# multi_sense32.net
KiCad netlist of a schematic drawn in EAGLE
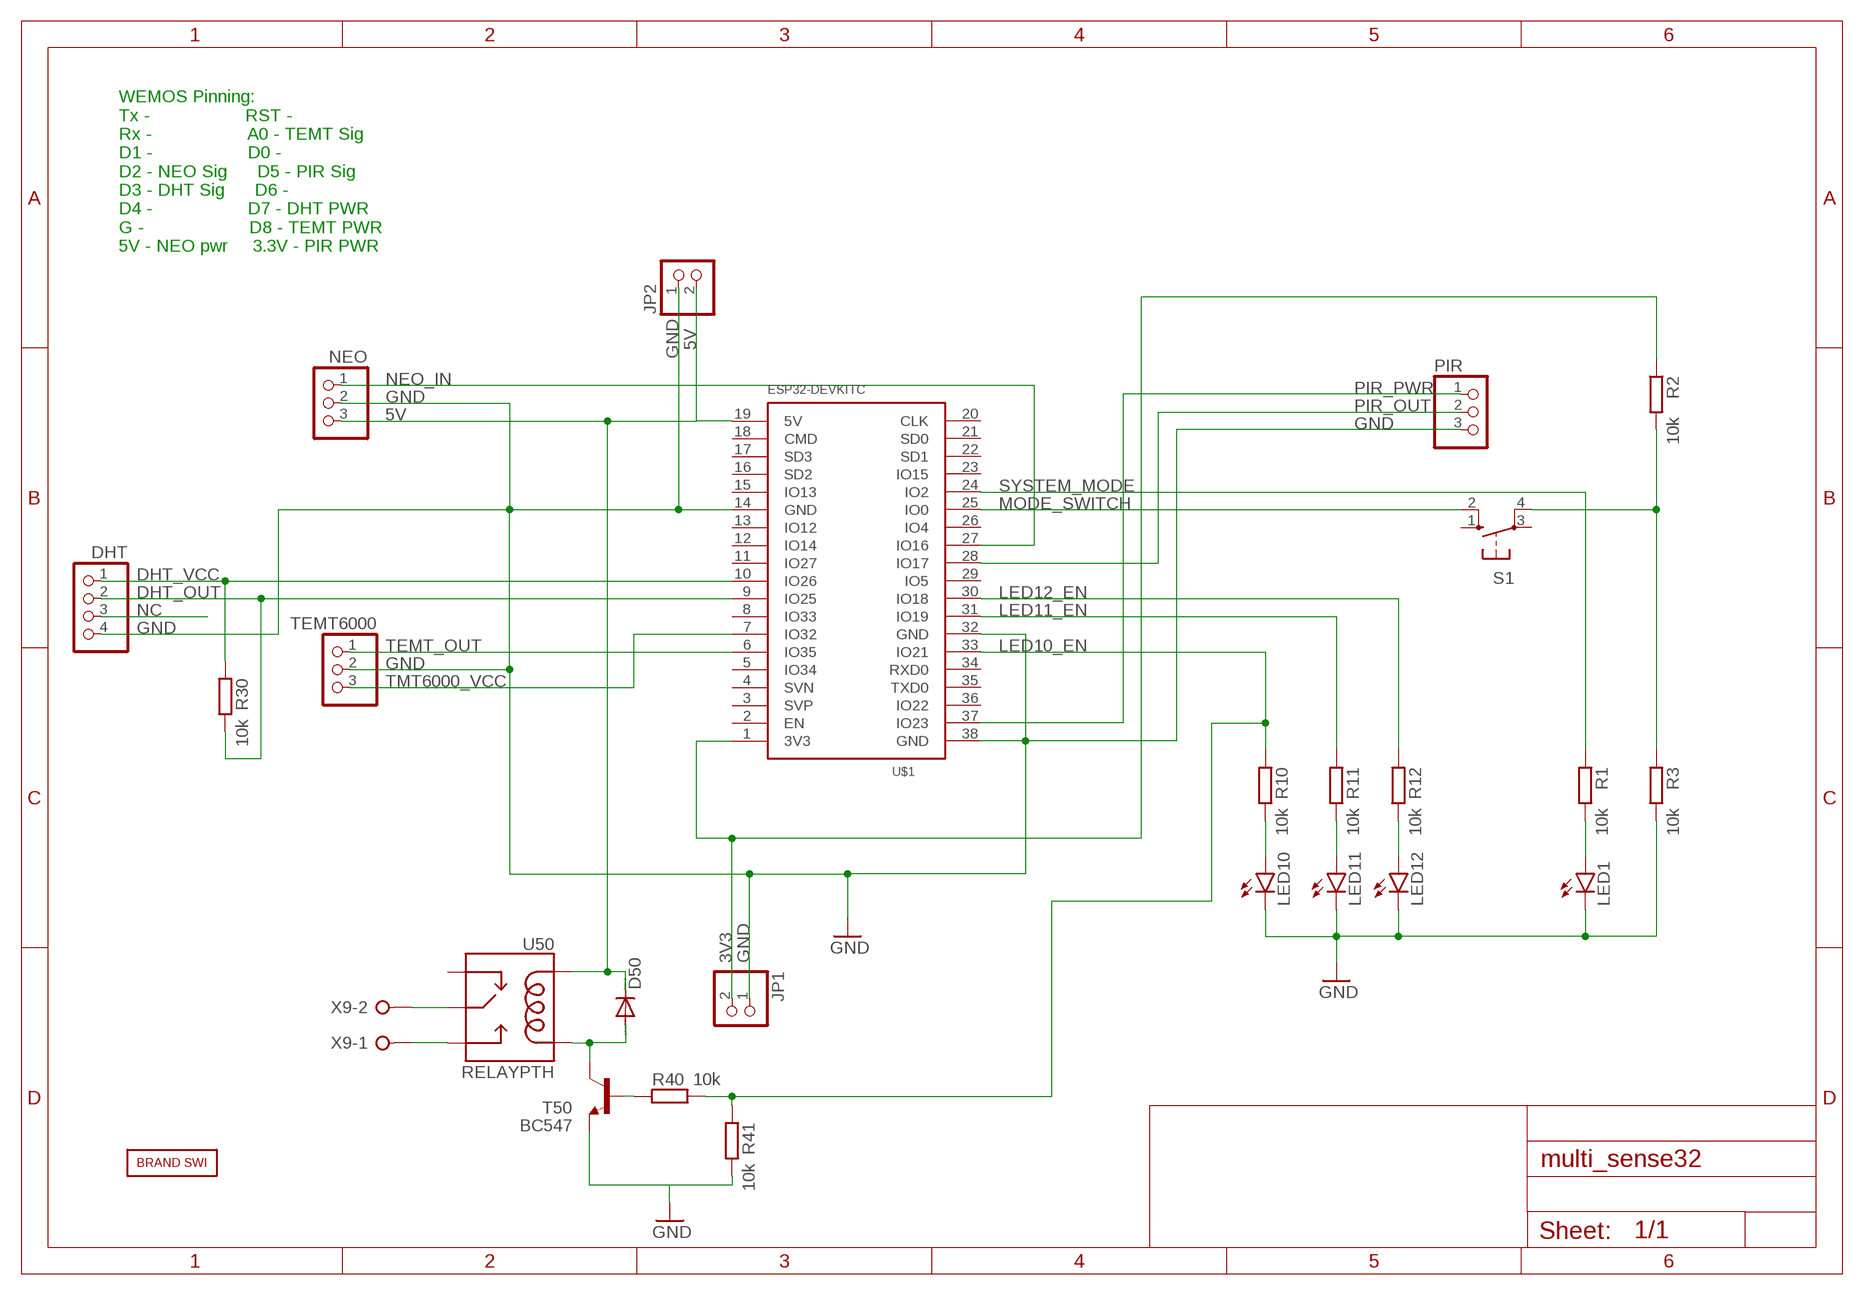
[diagram p0: schematic, sheet 1]

(export (version "E")
  (design (tool "Eeschema 10.0.6"))
  (components
    (comp (ref "D50")
      (value "1N4148DO35-7")
      (footprint "eagle-import:DO35-7")
      (libsource (lib "eagle-import") (part "1N4148DO35-7"))
    )
    (comp (ref "DHT")
      (value "PINHD-1X4")
      (footprint "eagle-import:1X04")
      (libsource (lib "eagle-import") (part "PINHD-1X4"))
    )
    (comp (ref "JP1")
      (value "PINHD-1X2")
      (footprint "eagle-import:1X02")
      (libsource (lib "eagle-import") (part "PINHD-1X2"))
    )
    (comp (ref "JP2")
      (value "PINHD-1X2")
      (footprint "eagle-import:1X02")
      (libsource (lib "eagle-import") (part "PINHD-1X2"))
    )
    (comp (ref "LED1")
      (value "LED3MM")
      (footprint "eagle-import:LED3MM")
      (libsource (lib "eagle-import") (part "LED3MM"))
    )
    (comp (ref "LED10")
      (value "LED3MM")
      (footprint "eagle-import:LED3MM")
      (libsource (lib "eagle-import") (part "LED3MM"))
    )
    (comp (ref "LED11")
      (value "LED3MM")
      (footprint "eagle-import:LED3MM")
      (libsource (lib "eagle-import") (part "LED3MM"))
    )
    (comp (ref "LED12")
      (value "LED3MM")
      (footprint "eagle-import:LED3MM")
      (libsource (lib "eagle-import") (part "LED3MM"))
    )
    (comp (ref "NEO")
      (value "PINHD-1X3")
      (footprint "eagle-import:1X03")
      (libsource (lib "eagle-import") (part "PINHD-1X3"))
    )
    (comp (ref "PIR")
      (value "PINHD-1X3")
      (footprint "eagle-import:1X03")
      (libsource (lib "eagle-import") (part "PINHD-1X3"))
    )
    (comp (ref "R1")
      (value "10k")
      (footprint "eagle-import:0207_10")
      (libsource (lib "eagle-import") (part "R-EU_0207/10"))
    )
    (comp (ref "R2")
      (value "10k")
      (footprint "eagle-import:0207_10")
      (libsource (lib "eagle-import") (part "R-EU_0207/10"))
    )
    (comp (ref "R3")
      (value "10k")
      (footprint "eagle-import:0207_10")
      (libsource (lib "eagle-import") (part "R-EU_0207/10"))
    )
    (comp (ref "R10")
      (value "10k")
      (footprint "eagle-import:0207_10")
      (libsource (lib "eagle-import") (part "R-EU_0207/10"))
    )
    (comp (ref "R11")
      (value "10k")
      (footprint "eagle-import:0207_10")
      (libsource (lib "eagle-import") (part "R-EU_0207/10"))
    )
    (comp (ref "R12")
      (value "10k")
      (footprint "eagle-import:0207_10")
      (libsource (lib "eagle-import") (part "R-EU_0207/10"))
    )
    (comp (ref "R30")
      (value "10k")
      (footprint "eagle-import:0207_10")
      (libsource (lib "eagle-import") (part "R-EU_0207/10"))
    )
    (comp (ref "R40")
      (value "10k")
      (footprint "eagle-import:0207_10")
      (libsource (lib "eagle-import") (part "R-EU_0207/10"))
    )
    (comp (ref "R41")
      (value "10k")
      (footprint "eagle-import:0207_10")
      (libsource (lib "eagle-import") (part "R-EU_0207/10"))
    )
    (comp (ref "S1")
      (value "10-XX")
      (footprint "eagle-import:B3F-10XX")
      (fields (field (name "MPN") "B3F-1000"))
      (libsource (lib "eagle-import") (part "10-XX"))
    )
    (comp (ref "T50")
      (value "BC547")
      (footprint "eagle-import:TO92")
      (libsource (lib "eagle-import") (part "BC547"))
    )
    (comp (ref "TEMT6000")
      (value "PINHD-1X3")
      (footprint "eagle-import:1X03")
      (libsource (lib "eagle-import") (part "PINHD-1X3"))
    )
    (comp (ref "U$1")
      (value "ESP32DEVKITC")
      (footprint "eagle-import:ESP32-DEVKITC")
      (libsource (lib "eagle-import") (part "ESP32DEVKITC"))
    )
    (comp (ref "U$2")
      (value "BRAND_SWI5X7")
      (footprint "eagle-import:BRAND_SWI_5X7")
      (libsource (lib "eagle-import") (part "BRAND_SWI5X7"))
    )
    (comp (ref "U50")
      (value "RELAYPTH")
      (footprint "eagle-import:SRD-05VDC-SL-C")
      (libsource (lib "eagle-import") (part "RELAYPTH"))
    )
    (comp (ref "X9")
      (value "W237-02P")
      (footprint "eagle-import:W237-132")
      (libsource (lib "eagle-import") (part "W237-02P"))
    )
  )
  (nets
    (net (code "1") (name "/3V3") (class "Default")
      (node (ref "JP1") (pin "2") (pinfunction "2_2") (pintype "passive"))
      (node (ref "R2") (pin "1") (pinfunction "1_1") (pintype "passive"))
      (node (ref "U$1") (pin "1") (pinfunction "3V3_1") (pintype "bidirectional"))
    )
    (net (code "2") (name "/5V") (class "Default")
      (node (ref "D50") (pin "C") (pinfunction "C_C") (pintype "passive"))
      (node (ref "JP2") (pin "2") (pinfunction "2_2") (pintype "passive"))
      (node (ref "NEO") (pin "3") (pinfunction "3_3") (pintype "passive"))
      (node (ref "U$1") (pin "19") (pinfunction "5V_19") (pintype "bidirectional"))
      (node (ref "U50") (pin "COIL1") (pinfunction "COIL1_COIL1") (pintype "bidirectional"))
    )
    (net (code "3") (name "/DHT_OUT") (class "Default")
      (node (ref "DHT") (pin "2") (pinfunction "2_2") (pintype "passive"))
      (node (ref "R30") (pin "2") (pinfunction "2_2") (pintype "passive"))
      (node (ref "U$1") (pin "9") (pinfunction "IO25_9") (pintype "bidirectional"))
    )
    (net (code "4") (name "/DHT_VCC") (class "Default")
      (node (ref "DHT") (pin "1") (pinfunction "1_1") (pintype "passive"))
      (node (ref "R30") (pin "1") (pinfunction "1_1") (pintype "passive"))
      (node (ref "U$1") (pin "10") (pinfunction "IO26_10") (pintype "bidirectional"))
    )
    (net (code "5") (name "/LED10_EN") (class "Default")
      (node (ref "R10") (pin "1") (pinfunction "1_1") (pintype "passive"))
      (node (ref "R40") (pin "2") (pinfunction "2_2") (pintype "passive"))
      (node (ref "R41") (pin "1") (pinfunction "1_1") (pintype "passive"))
      (node (ref "U$1") (pin "33") (pinfunction "IO21_33") (pintype "bidirectional"))
    )
    (net (code "6") (name "/LED11_EN") (class "Default")
      (node (ref "R11") (pin "1") (pinfunction "1_1") (pintype "passive"))
      (node (ref "U$1") (pin "31") (pinfunction "IO19_31") (pintype "bidirectional"))
    )
    (net (code "7") (name "/LED12_EN") (class "Default")
      (node (ref "R12") (pin "1") (pinfunction "1_1") (pintype "passive"))
      (node (ref "U$1") (pin "30") (pinfunction "IO18_30") (pintype "bidirectional"))
    )
    (net (code "8") (name "/MODE_SWITCH") (class "Default")
      (node (ref "S1") (pin "2") (pinfunction "S1_2") (pintype "passive"))
      (node (ref "U$1") (pin "25") (pinfunction "IO0_25") (pintype "bidirectional"))
    )
    (net (code "9") (name "/NC") (class "Default")
      (node (ref "DHT") (pin "3") (pinfunction "3_3") (pintype "passive"))
    )
    (net (code "10") (name "/NEO_IN") (class "Default")
      (node (ref "NEO") (pin "1") (pinfunction "1_1") (pintype "passive"))
      (node (ref "U$1") (pin "27") (pinfunction "IO16_27") (pintype "bidirectional"))
    )
    (net (code "11") (name "/PIR_OUT") (class "Default")
      (node (ref "PIR") (pin "2") (pinfunction "2_2") (pintype "passive"))
      (node (ref "U$1") (pin "28") (pinfunction "IO17_28") (pintype "bidirectional"))
    )
    (net (code "12") (name "/PIR_PWR") (class "Default")
      (node (ref "PIR") (pin "1") (pinfunction "1_1") (pintype "passive"))
      (node (ref "U$1") (pin "37") (pinfunction "IO23_37") (pintype "bidirectional"))
    )
    (net (code "13") (name "/SYSTEM_MODE") (class "Default")
      (node (ref "R1") (pin "1") (pinfunction "1_1") (pintype "passive"))
      (node (ref "U$1") (pin "24") (pinfunction "IO2_24") (pintype "bidirectional"))
    )
    (net (code "14") (name "/TEMT_OUT") (class "Default")
      (node (ref "TEMT6000") (pin "1") (pinfunction "1_1") (pintype "passive"))
      (node (ref "U$1") (pin "6") (pinfunction "IO35_6") (pintype "bidirectional"))
    )
    (net (code "15") (name "/TMT6000_VCC") (class "Default")
      (node (ref "TEMT6000") (pin "3") (pinfunction "3_3") (pintype "passive"))
      (node (ref "U$1") (pin "7") (pinfunction "IO32_7") (pintype "bidirectional"))
    )
    (net (code "16") (name "GND") (class "Default")
      (node (ref "DHT") (pin "4") (pinfunction "4_4") (pintype "passive"))
      (node (ref "JP1") (pin "1") (pinfunction "1_1") (pintype "passive"))
      (node (ref "JP2") (pin "1") (pinfunction "1_1") (pintype "passive"))
      (node (ref "LED1") (pin "K") (pinfunction "C_K") (pintype "passive"))
      (node (ref "LED10") (pin "K") (pinfunction "C_K") (pintype "passive"))
      (node (ref "LED11") (pin "K") (pinfunction "C_K") (pintype "passive"))
      (node (ref "LED12") (pin "K") (pinfunction "C_K") (pintype "passive"))
      (node (ref "NEO") (pin "2") (pinfunction "2_2") (pintype "passive"))
      (node (ref "PIR") (pin "3") (pinfunction "3_3") (pintype "passive"))
      (node (ref "R3") (pin "2") (pinfunction "2_2") (pintype "passive"))
      (node (ref "R41") (pin "2") (pinfunction "2_2") (pintype "passive"))
      (node (ref "T50") (pin "1") (pinfunction "E_1") (pintype "passive"))
      (node (ref "TEMT6000") (pin "2") (pinfunction "2_2") (pintype "passive"))
      (node (ref "U$1") (pin "14") (pinfunction "GND_14") (pintype "bidirectional"))
      (node (ref "U$1") (pin "32") (pinfunction "GND_32") (pintype "bidirectional"))
      (node (ref "U$1") (pin "38") (pinfunction "GND_38") (pintype "bidirectional"))
    )
    (net (code "17") (name "Net-(LED1-PadA)") (class "Default")
      (node (ref "LED1") (pin "A") (pinfunction "A_A") (pintype "passive"))
      (node (ref "R1") (pin "2") (pinfunction "2_2") (pintype "passive"))
    )
    (net (code "18") (name "Net-(LED10-PadA)") (class "Default")
      (node (ref "LED10") (pin "A") (pinfunction "A_A") (pintype "passive"))
      (node (ref "R10") (pin "2") (pinfunction "2_2") (pintype "passive"))
    )
    (net (code "19") (name "Net-(LED11-PadA)") (class "Default")
      (node (ref "LED11") (pin "A") (pinfunction "A_A") (pintype "passive"))
      (node (ref "R11") (pin "2") (pinfunction "2_2") (pintype "passive"))
    )
    (net (code "20") (name "Net-(LED12-PadA)") (class "Default")
      (node (ref "LED12") (pin "A") (pinfunction "A_A") (pintype "passive"))
      (node (ref "R12") (pin "2") (pinfunction "2_2") (pintype "passive"))
    )
    (net (code "21") (name "Net-(S1-P1)") (class "Default")
      (node (ref "R2") (pin "2") (pinfunction "2_2") (pintype "passive"))
      (node (ref "R3") (pin "1") (pinfunction "1_1") (pintype "passive"))
      (node (ref "S1") (pin "4") (pinfunction "P1_4") (pintype "passive"))
    )
    (net (code "22") (name "Net-(T50-B)") (class "Default")
      (node (ref "R40") (pin "1") (pinfunction "1_1") (pintype "passive"))
      (node (ref "T50") (pin "2") (pinfunction "B_2") (pintype "passive"))
    )
    (net (code "23") (name "Net-(T50-C)") (class "Default")
      (node (ref "D50") (pin "A") (pinfunction "A_A") (pintype "passive"))
      (node (ref "T50") (pin "3") (pinfunction "C_3") (pintype "passive"))
      (node (ref "U50") (pin "COIL0") (pinfunction "COIL0_COIL0") (pintype "bidirectional"))
    )
    (net (code "24") (name "Net-(X9A-KL)") (class "Default")
      (node (ref "U50") (pin "SWOPEN") (pinfunction "SWOPEN_SWOPEN") (pintype "bidirectional"))
      (node (ref "X9") (pin "1") (pinfunction "KL_1") (pintype "passive"))
    )
    (net (code "25") (name "Net-(X9B-KL)") (class "Default")
      (node (ref "U50") (pin "SWCOMMON") (pinfunction "SWCOMMON_SWCOMMON") (pintype "bidirectional"))
      (node (ref "X9") (pin "2") (pinfunction "KL_2") (pintype "passive"))
    )
    (net (code "26") (name "unconnected-(S1-P-Pad3)") (class "Default")
      (node (ref "S1") (pin "3") (pinfunction "P_3") (pintype "passive"))
    )
    (net (code "27") (name "unconnected-(S1-S-Pad1)") (class "Default")
      (node (ref "S1") (pin "1") (pinfunction "S_1") (pintype "passive"))
    )
    (net (code "28") (name "unconnected-(U$1-CLK-Pad20)") (class "Default")
      (node (ref "U$1") (pin "20") (pinfunction "CLK_20") (pintype "bidirectional"))
    )
    (net (code "29") (name "unconnected-(U$1-CMD-Pad18)") (class "Default")
      (node (ref "U$1") (pin "18") (pinfunction "CMD_18") (pintype "bidirectional"))
    )
    (net (code "30") (name "unconnected-(U$1-EN-Pad2)") (class "Default")
      (node (ref "U$1") (pin "2") (pinfunction "EN_2") (pintype "bidirectional"))
    )
    (net (code "31") (name "unconnected-(U$1-IO4-Pad26)") (class "Default")
      (node (ref "U$1") (pin "26") (pinfunction "IO4_26") (pintype "bidirectional"))
    )
    (net (code "32") (name "unconnected-(U$1-IO5-Pad29)") (class "Default")
      (node (ref "U$1") (pin "29") (pinfunction "IO5_29") (pintype "bidirectional"))
    )
    (net (code "33") (name "unconnected-(U$1-IO12-Pad13)") (class "Default")
      (node (ref "U$1") (pin "13") (pinfunction "IO12_13") (pintype "bidirectional"))
    )
    (net (code "34") (name "unconnected-(U$1-IO13-Pad15)") (class "Default")
      (node (ref "U$1") (pin "15") (pinfunction "IO13_15") (pintype "bidirectional"))
    )
    (net (code "35") (name "unconnected-(U$1-IO14-Pad12)") (class "Default")
      (node (ref "U$1") (pin "12") (pinfunction "IO14_12") (pintype "bidirectional"))
    )
    (net (code "36") (name "unconnected-(U$1-IO15-Pad23)") (class "Default")
      (node (ref "U$1") (pin "23") (pinfunction "IO15_23") (pintype "bidirectional"))
    )
    (net (code "37") (name "unconnected-(U$1-IO22-Pad36)") (class "Default")
      (node (ref "U$1") (pin "36") (pinfunction "IO22_36") (pintype "bidirectional"))
    )
    (net (code "38") (name "unconnected-(U$1-IO27-Pad11)") (class "Default")
      (node (ref "U$1") (pin "11") (pinfunction "IO27_11") (pintype "bidirectional"))
    )
    (net (code "39") (name "unconnected-(U$1-IO33-Pad8)") (class "Default")
      (node (ref "U$1") (pin "8") (pinfunction "IO33_8") (pintype "bidirectional"))
    )
    (net (code "40") (name "unconnected-(U$1-IO34-Pad5)") (class "Default")
      (node (ref "U$1") (pin "5") (pinfunction "IO34_5") (pintype "bidirectional"))
    )
    (net (code "41") (name "unconnected-(U$1-RXD0-Pad34)") (class "Default")
      (node (ref "U$1") (pin "34") (pinfunction "RXD0_34") (pintype "bidirectional"))
    )
    (net (code "42") (name "unconnected-(U$1-SD0-Pad21)") (class "Default")
      (node (ref "U$1") (pin "21") (pinfunction "SD0_21") (pintype "bidirectional"))
    )
    (net (code "43") (name "unconnected-(U$1-SD1-Pad22)") (class "Default")
      (node (ref "U$1") (pin "22") (pinfunction "SD1_22") (pintype "bidirectional"))
    )
    (net (code "44") (name "unconnected-(U$1-SD2-Pad16)") (class "Default")
      (node (ref "U$1") (pin "16") (pinfunction "SD2_16") (pintype "bidirectional"))
    )
    (net (code "45") (name "unconnected-(U$1-SD3-Pad17)") (class "Default")
      (node (ref "U$1") (pin "17") (pinfunction "SD3_17") (pintype "bidirectional"))
    )
    (net (code "46") (name "unconnected-(U$1-SVN-Pad4)") (class "Default")
      (node (ref "U$1") (pin "4") (pinfunction "SVN_4") (pintype "bidirectional"))
    )
    (net (code "47") (name "unconnected-(U$1-SVP-Pad3)") (class "Default")
      (node (ref "U$1") (pin "3") (pinfunction "SVP_3") (pintype "bidirectional"))
    )
    (net (code "48") (name "unconnected-(U$1-TXD0-Pad35)") (class "Default")
      (node (ref "U$1") (pin "35") (pinfunction "TXD0_35") (pintype "bidirectional"))
    )
    (net (code "49") (name "unconnected-(U50-SWCLOSE-PadSWCLOSED)") (class "Default")
      (node (ref "U50") (pin "SWCLOSED") (pinfunction "SWCLOSE_SWCLOSED") (pintype "bidirectional"))
    )
  )
)
